# Relay_Module_Schematic.net
KiCad netlist of a schematic drawn in Altium Designer
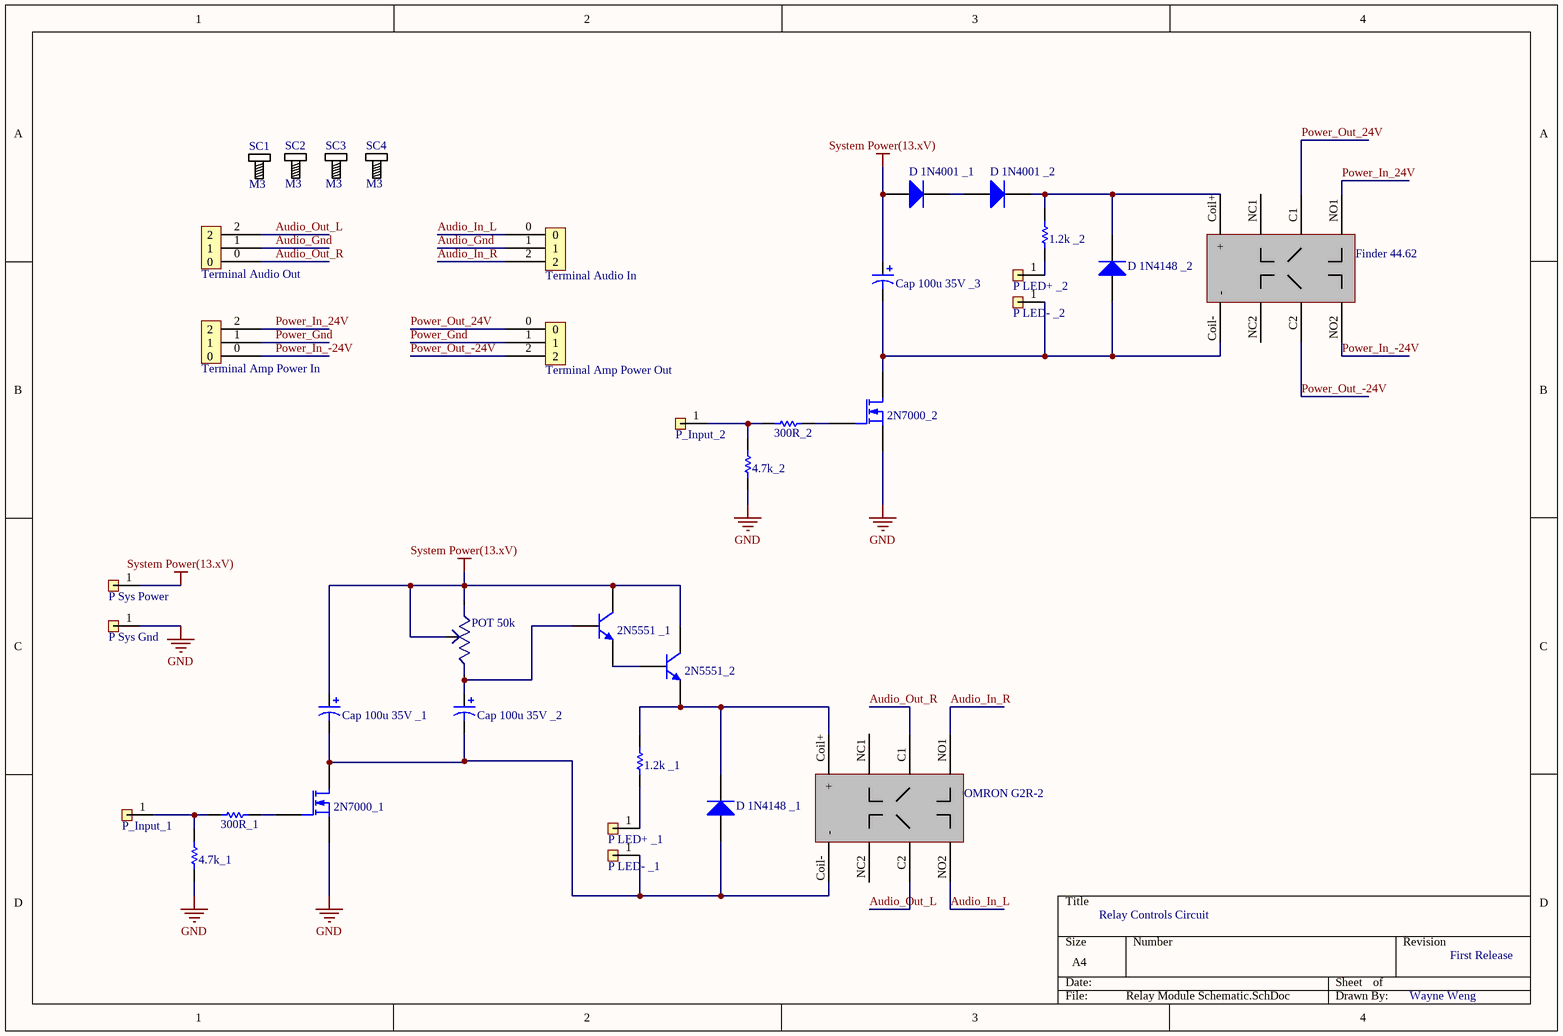
[diagram p0: Relay Module Schematic.SchDoc]

(export (version "E")
  (design (tool "Eeschema 10.0.6"))
  (components
    (comp (ref "1.2k _1")
      (value "Resistor SMD 0805")
      (footprint "Relay Module:RES_0805")
      (fields (field (name "PUBLISHER") "Altium Limited"))
      (libsource (lib "Relay Module") (part "Resistor SMD 0805"))
    )
    (comp (ref "1.2k _2")
      (value "Resistor SMD 0805")
      (footprint "Relay Module:RES_0805")
      (fields (field (name "PUBLISHER") "Altium Limited"))
      (libsource (lib "Relay Module") (part "Resistor SMD 0805"))
    )
    (comp (ref "2N5551 _1")
      (value "2N5551")
      (footprint "Relay Module:2N5551")
      (description "NPN 2N5551 General Purpose Amplifier")
      (libsource (lib "Relay Module") (part "2N5551"))
    )
    (comp (ref "2N5551_2")
      (value "2N5551")
      (footprint "Relay Module:2N5551")
      (description "NPN 2N5551 General Purpose Amplifier")
      (libsource (lib "Relay Module") (part "2N5551"))
    )
    (comp (ref "2N7000_1")
      (value "2N7000")
      (footprint "Relay Module:2N7000")
      (description "2N7000 TO-92")
      (libsource (lib "Relay Module") (part "2N7000"))
    )
    (comp (ref "2N7000_2")
      (value "2N7000")
      (footprint "Relay Module:2N7000")
      (description "2N7000 TO-92")
      (libsource (lib "Relay Module") (part "2N7000"))
    )
    (comp (ref "4.7k_1")
      (value "Resistor SMD 0805")
      (footprint "Relay Module:RES_0805")
      (fields (field (name "PUBLISHER") "Altium Limited"))
      (libsource (lib "Relay Module") (part "Resistor SMD 0805"))
    )
    (comp (ref "4.7k_2")
      (value "Resistor SMD 0805")
      (footprint "Relay Module:RES_0805")
      (fields (field (name "PUBLISHER") "Altium Limited"))
      (libsource (lib "Relay Module") (part "Resistor SMD 0805"))
    )
    (comp (ref "300R_1")
      (value "Resistor SMD 0805")
      (footprint "Relay Module:RES_0805")
      (fields (field (name "PUBLISHER") "Altium Limited"))
      (libsource (lib "Relay Module") (part "Resistor SMD 0805"))
    )
    (comp (ref "300R_2")
      (value "Resistor SMD 0805")
      (footprint "Relay Module:RES_0805")
      (fields (field (name "PUBLISHER") "Altium Limited"))
      (libsource (lib "Relay Module") (part "Resistor SMD 0805"))
    )
    (comp (ref "Cap 100u 35V _1")
      (value "Cap")
      (footprint "Relay Module:Radial Capacitor 3.5mm Pitch")
      (description "Cap Radial 8*11 3.5mm Pitch")
      (libsource (lib "Relay Module") (part "Cap Radial 8*11 3.5mm Pitch"))
    )
    (comp (ref "Cap 100u 35V _2")
      (value "Cap")
      (footprint "Relay Module:Radial Capacitor 3.5mm Pitch")
      (description "Cap Radial 8*11 3.5mm Pitch")
      (libsource (lib "Relay Module") (part "Cap Radial 8*11 3.5mm Pitch"))
    )
    (comp (ref "Cap 100u 35V _3")
      (value "Cap")
      (footprint "Relay Module:Radial Capacitor 3.5mm Pitch")
      (description "Cap Radial 8*11 3.5mm Pitch")
      (libsource (lib "Relay Module") (part "Cap Radial 8*11 3.5mm Pitch"))
    )
    (comp (ref "D 1N4001 _1")
      (value "Diode 1N4001")
      (footprint "Relay Module:DO-41")
      (description "1 Amp General Purpose Rectifier")
      (fields (field (name "PUBLISHER") "Altium Limited"))
      (libsource (lib "Relay Module") (part "Diode 1N4001"))
    )
    (comp (ref "D 1N4001 _2")
      (value "Diode 1N4001")
      (footprint "Relay Module:DO-41")
      (description "1 Amp General Purpose Rectifier")
      (fields (field (name "PUBLISHER") "Altium Limited"))
      (libsource (lib "Relay Module") (part "Diode 1N4001"))
    )
    (comp (ref "D 1N4148 _1")
      (value "Diode 1N4148")
      (footprint "Relay Module:DO-35")
      (description "High Conductance Fast Diode")
      (fields (field (name "PUBLISHER") "Altium Limited"))
      (libsource (lib "Relay Module") (part "Diode 1N4148"))
    )
    (comp (ref "D 1N4148 _2")
      (value "Diode 1N4148")
      (footprint "Relay Module:DO-35")
      (description "High Conductance Fast Diode")
      (fields (field (name "PUBLISHER") "Altium Limited"))
      (libsource (lib "Relay Module") (part "Diode 1N4148"))
    )
    (comp (ref "Finder 44.62")
      (value "Finder 44.62")
      (footprint "Relay Module:Finder 44.62")
      (description "Finder 44.62 PCB Relay")
      (libsource (lib "Relay Module") (part "Finder 44.62"))
    )
    (comp (ref "OMRON G2R-2")
      (value "OMRON G2R-2")
      (footprint "Relay Module:OMRON G2R-2 - Brown")
      (description "OMRON G2R-2 Power Relay DPDT")
      (libsource (lib "Relay Module") (part "OMRON G2R-2"))
    )
    (comp (ref "P LED+ _1")
      (value "Header 1 Pin")
      (footprint "Relay Module:HDR1X1_180_2.54")
      (libsource (lib "Relay Module") (part "Header 1 Pin"))
    )
    (comp (ref "P LED+ _2")
      (value "Header 1 Pin")
      (footprint "Relay Module:HDR1X1_180_2.54")
      (libsource (lib "Relay Module") (part "Header 1 Pin"))
    )
    (comp (ref "P LED- _1")
      (value "Header 1 Pin")
      (footprint "Relay Module:HDR1X1_180_2.54")
      (libsource (lib "Relay Module") (part "Header 1 Pin"))
    )
    (comp (ref "P LED- _2")
      (value "Header 1 Pin")
      (footprint "Relay Module:HDR1X1_180_2.54")
      (libsource (lib "Relay Module") (part "Header 1 Pin"))
    )
    (comp (ref "P Sys Gnd")
      (value "Header 1 Pin")
      (footprint "Relay Module:HDR1X1_180_2.54")
      (libsource (lib "Relay Module") (part "Header 1 Pin"))
    )
    (comp (ref "P Sys Power")
      (value "Header 1 Pin")
      (footprint "Relay Module:HDR1X1_180_2.54")
      (libsource (lib "Relay Module") (part "Header 1 Pin"))
    )
    (comp (ref "POT 50k")
      (value "BOURNS 3296")
      (footprint "Relay Module:Potentiometer 25 Turn")
      (libsource (lib "Relay Module") (part "BOURNS 3296"))
    )
    (comp (ref "P_Input_1")
      (value "Header 1 Pin")
      (footprint "Relay Module:HDR1X1_180_2.54")
      (libsource (lib "Relay Module") (part "Header 1 Pin"))
    )
    (comp (ref "P_Input_2")
      (value "Header 1 Pin")
      (footprint "Relay Module:HDR1X1_180_2.54")
      (libsource (lib "Relay Module") (part "Header 1 Pin"))
    )
    (comp (ref "SC1")
      (value "M3")
      (footprint "Relay Module:SCRREW_M3")
      (description "Screw")
      (libsource (lib "Relay Module") (part "Screw_M3"))
    )
    (comp (ref "SC2")
      (value "M3")
      (footprint "Relay Module:SCRREW_M3")
      (description "Screw")
      (libsource (lib "Relay Module") (part "Screw_M3"))
    )
    (comp (ref "SC3")
      (value "M3")
      (footprint "Relay Module:SCRREW_M3")
      (description "Screw")
      (libsource (lib "Relay Module") (part "Screw_M3"))
    )
    (comp (ref "SC4")
      (value "M3")
      (footprint "Relay Module:SCRREW_M3")
      (description "Screw")
      (libsource (lib "Relay Module") (part "Screw_M3"))
    )
    (comp (ref "Terminal Amp Power In")
      (value "3P Terminal Block")
      (footprint "Relay Module:3P Terminal Block")
      (description "Howder 3P Terminal Block HD-816-3P")
      (libsource (lib "") (part "3P Terminal Block_1"))
    )
    (comp (ref "Terminal Amp Power Out")
      (value "3P Terminal Block")
      (footprint "Relay Module:3P Terminal Block")
      (description "Howder 3P Terminal Block HD-816-3P")
      (libsource (lib "Relay Module") (part "3P Terminal Block"))
    )
    (comp (ref "Terminal Audio In")
      (value "3P Terminal Block")
      (footprint "Relay Module:3P Terminal Block")
      (description "Howder 3P Terminal Block HD-816-3P")
      (libsource (lib "Relay Module") (part "3P Terminal Block"))
    )
    (comp (ref "Terminal Audio Out")
      (value "3P Terminal Block")
      (footprint "Relay Module:3P Terminal Block")
      (description "Howder 3P Terminal Block HD-816-3P")
      (libsource (lib "") (part "3P Terminal Block_1"))
    )
  )
  (nets
    (net (code "1") (name "/Audio_Gnd") (class "Default")
      (node (ref "Terminal Audio In") (pin "1") (pinfunction "1_1") (pintype "passive"))
      (node (ref "Terminal Audio Out") (pin "1") (pinfunction "1_1") (pintype "passive"))
    )
    (net (code "2") (name "/Audio_In_L") (class "Default")
      (node (ref "OMRON G2R-2") (pin "NO2") (pinfunction "NO2_NO2") (pintype "passive"))
      (node (ref "Terminal Audio In") (pin "0") (pinfunction "0_0") (pintype "passive"))
    )
    (net (code "3") (name "/Audio_In_R") (class "Default")
      (node (ref "OMRON G2R-2") (pin "NO1") (pinfunction "NO1_NO1") (pintype "passive"))
      (node (ref "Terminal Audio In") (pin "2") (pinfunction "2_2") (pintype "passive"))
    )
    (net (code "4") (name "/Audio_Out_L") (class "Default")
      (node (ref "OMRON G2R-2") (pin "C2") (pinfunction "C2_C2") (pintype "passive"))
      (node (ref "Terminal Audio Out") (pin "2") (pinfunction "2_2") (pintype "passive"))
    )
    (net (code "5") (name "/Audio_Out_R") (class "Default")
      (node (ref "OMRON G2R-2") (pin "C1") (pinfunction "NC_C1") (pintype "passive"))
      (node (ref "Terminal Audio Out") (pin "0") (pinfunction "0_0") (pintype "passive"))
    )
    (net (code "6") (name "/Power_Gnd") (class "Default")
      (node (ref "Terminal Amp Power In") (pin "1") (pinfunction "1_1") (pintype "passive"))
      (node (ref "Terminal Amp Power Out") (pin "1") (pinfunction "1_1") (pintype "passive"))
    )
    (net (code "7") (name "/Power_In_-24V") (class "Default")
      (node (ref "Finder 44.62") (pin "NO2") (pinfunction "NO2_NO2") (pintype "passive"))
      (node (ref "Terminal Amp Power In") (pin "0") (pinfunction "0_0") (pintype "passive"))
    )
    (net (code "8") (name "/Power_In_24V") (class "Default")
      (node (ref "Finder 44.62") (pin "NO1") (pinfunction "NO1_NO1") (pintype "passive"))
      (node (ref "Terminal Amp Power In") (pin "2") (pinfunction "2_2") (pintype "passive"))
    )
    (net (code "9") (name "/Power_Out_-24V") (class "Default")
      (node (ref "Finder 44.62") (pin "C2") (pinfunction "C2_C2") (pintype "passive"))
      (node (ref "Terminal Amp Power Out") (pin "2") (pinfunction "2_2") (pintype "passive"))
    )
    (net (code "10") (name "/Power_Out_24V") (class "Default")
      (node (ref "Finder 44.62") (pin "C1") (pinfunction "NC_C1") (pintype "passive"))
      (node (ref "Terminal Amp Power Out") (pin "0") (pinfunction "0_0") (pintype "passive"))
    )
    (net (code "11") (name "GND") (class "Default")
      (node (ref "2N7000_1") (pin "1") (pinfunction "S_1") (pintype "passive"))
      (node (ref "2N7000_2") (pin "1") (pinfunction "S_1") (pintype "passive"))
      (node (ref "4.7k_1") (pin "1") (pinfunction "1_1") (pintype "passive"))
      (node (ref "4.7k_2") (pin "1") (pinfunction "1_1") (pintype "passive"))
      (node (ref "P Sys Gnd") (pin "1") (pinfunction "1_1") (pintype "passive"))
    )
    (net (code "12") (name "Net-(1.2k _1-Pad1)") (class "Default")
      (node (ref "1.2k _1") (pin "1") (pinfunction "1_1") (pintype "passive"))
      (node (ref "P LED+ _1") (pin "1") (pinfunction "1_1") (pintype "passive"))
    )
    (net (code "13") (name "Net-(1.2k _2-Pad1)") (class "Default")
      (node (ref "1.2k _2") (pin "1") (pinfunction "1_1") (pintype "passive"))
      (node (ref "P LED+ _2") (pin "1") (pinfunction "1_1") (pintype "passive"))
    )
    (net (code "14") (name "Net-(2N5551 _1-B)") (class "Default")
      (node (ref "2N5551 _1") (pin "2") (pinfunction "B_2") (pintype "passive"))
      (node (ref "Cap 100u 35V _2") (pin "0") (pintype "passive"))
      (node (ref "POT 50k") (pin "1") (pintype "passive"))
    )
    (net (code "15") (name "Net-(2N5551 _1-E)") (class "Default")
      (node (ref "2N5551 _1") (pin "1") (pinfunction "E_1") (pintype "passive"))
      (node (ref "2N5551_2") (pin "2") (pinfunction "B_2") (pintype "passive"))
    )
    (net (code "16") (name "Net-(2N5551_2-E)") (class "Default")
      (node (ref "1.2k _1") (pin "2") (pinfunction "2_2") (pintype "passive"))
      (node (ref "2N5551_2") (pin "1") (pinfunction "E_1") (pintype "passive"))
      (node (ref "D 1N4148 _1") (pin "2") (pinfunction "K_2") (pintype "passive"))
      (node (ref "OMRON G2R-2") (pin "Coil+") (pinfunction "+_Coil+") (pintype "passive"))
    )
    (net (code "17") (name "Net-(2N7000_1-D)") (class "Default")
      (node (ref "2N7000_1") (pin "3") (pinfunction "D_3") (pintype "passive"))
      (node (ref "Cap 100u 35V _1") (pin "1") (pintype "passive"))
      (node (ref "Cap 100u 35V _2") (pin "1") (pintype "passive"))
      (node (ref "D 1N4148 _1") (pin "1") (pinfunction "A_1") (pintype "passive"))
      (node (ref "OMRON G2R-2") (pin "Coil-") (pinfunction "-_Coil-") (pintype "passive"))
      (node (ref "P LED- _1") (pin "1") (pinfunction "1_1") (pintype "passive"))
    )
    (net (code "18") (name "Net-(2N7000_1-G)") (class "Default")
      (node (ref "2N7000_1") (pin "2") (pinfunction "G_2") (pintype "passive"))
      (node (ref "300R_1") (pin "2") (pinfunction "2_2") (pintype "passive"))
    )
    (net (code "19") (name "Net-(2N7000_2-D)") (class "Default")
      (node (ref "2N7000_2") (pin "3") (pinfunction "D_3") (pintype "passive"))
      (node (ref "Cap 100u 35V _3") (pin "1") (pintype "passive"))
      (node (ref "D 1N4148 _2") (pin "1") (pinfunction "A_1") (pintype "passive"))
      (node (ref "Finder 44.62") (pin "Coil-") (pinfunction "-_Coil-") (pintype "passive"))
      (node (ref "P LED- _2") (pin "1") (pinfunction "1_1") (pintype "passive"))
    )
    (net (code "20") (name "Net-(2N7000_2-G)") (class "Default")
      (node (ref "2N7000_2") (pin "2") (pinfunction "G_2") (pintype "passive"))
      (node (ref "300R_2") (pin "2") (pinfunction "2_2") (pintype "passive"))
    )
    (net (code "21") (name "Net-(300R_1-Pad1)") (class "Default")
      (node (ref "300R_1") (pin "1") (pinfunction "1_1") (pintype "passive"))
      (node (ref "4.7k_1") (pin "2") (pinfunction "2_2") (pintype "passive"))
      (node (ref "P_Input_1") (pin "1") (pinfunction "1_1") (pintype "passive"))
    )
    (net (code "22") (name "Net-(300R_2-Pad1)") (class "Default")
      (node (ref "300R_2") (pin "1") (pinfunction "1_1") (pintype "passive"))
      (node (ref "4.7k_2") (pin "2") (pinfunction "2_2") (pintype "passive"))
      (node (ref "P_Input_2") (pin "1") (pinfunction "1_1") (pintype "passive"))
    )
    (net (code "23") (name "Net-(D 1N4001 _1-K)") (class "Default")
      (node (ref "D 1N4001 _1") (pin "2") (pinfunction "K_2") (pintype "passive"))
      (node (ref "D 1N4001 _2") (pin "1") (pinfunction "A_1") (pintype "passive"))
    )
    (net (code "24") (name "Net-(D 1N4001 _2-K)") (class "Default")
      (node (ref "1.2k _2") (pin "2") (pinfunction "2_2") (pintype "passive"))
      (node (ref "D 1N4001 _2") (pin "2") (pinfunction "K_2") (pintype "passive"))
      (node (ref "D 1N4148 _2") (pin "2") (pinfunction "K_2") (pintype "passive"))
      (node (ref "Finder 44.62") (pin "Coil+") (pinfunction "+_Coil+") (pintype "passive"))
    )
    (net (code "25") (name "System Power(13.xV)") (class "Default")
      (node (ref "2N5551 _1") (pin "3") (pinfunction "C_3") (pintype "passive"))
      (node (ref "2N5551_2") (pin "3") (pinfunction "C_3") (pintype "passive"))
      (node (ref "Cap 100u 35V _1") (pin "0") (pintype "passive"))
      (node (ref "Cap 100u 35V _3") (pin "0") (pintype "passive"))
      (node (ref "D 1N4001 _1") (pin "1") (pinfunction "A_1") (pintype "passive"))
      (node (ref "P Sys Power") (pin "1") (pinfunction "1_1") (pintype "passive"))
      (node (ref "POT 50k") (pin "2") (pintype "passive"))
      (node (ref "POT 50k") (pin "3") (pintype "passive"))
    )
    (net (code "26") (name "unconnected-(Finder 44.62-2-PadNC1)") (class "Default")
      (node (ref "Finder 44.62") (pin "NC1") (pinfunction "2_NC1") (pintype "passive"))
    )
    (net (code "27") (name "unconnected-(Finder 44.62-PadNC2)") (class "Default")
      (node (ref "Finder 44.62") (pin "NC2") (pinfunction "NC2_NC2") (pintype "passive"))
    )
    (net (code "28") (name "unconnected-(OMRON G2R-2-2-PadNC1)") (class "Default")
      (node (ref "OMRON G2R-2") (pin "NC1") (pinfunction "2_NC1") (pintype "passive"))
    )
    (net (code "29") (name "unconnected-(OMRON G2R-2-PadNC2)") (class "Default")
      (node (ref "OMRON G2R-2") (pin "NC2") (pinfunction "NC2_NC2") (pintype "passive"))
    )
  )
)
